# SNAC_7ch_SNES.net
KiCad netlist of a schematic drawn in EAGLE
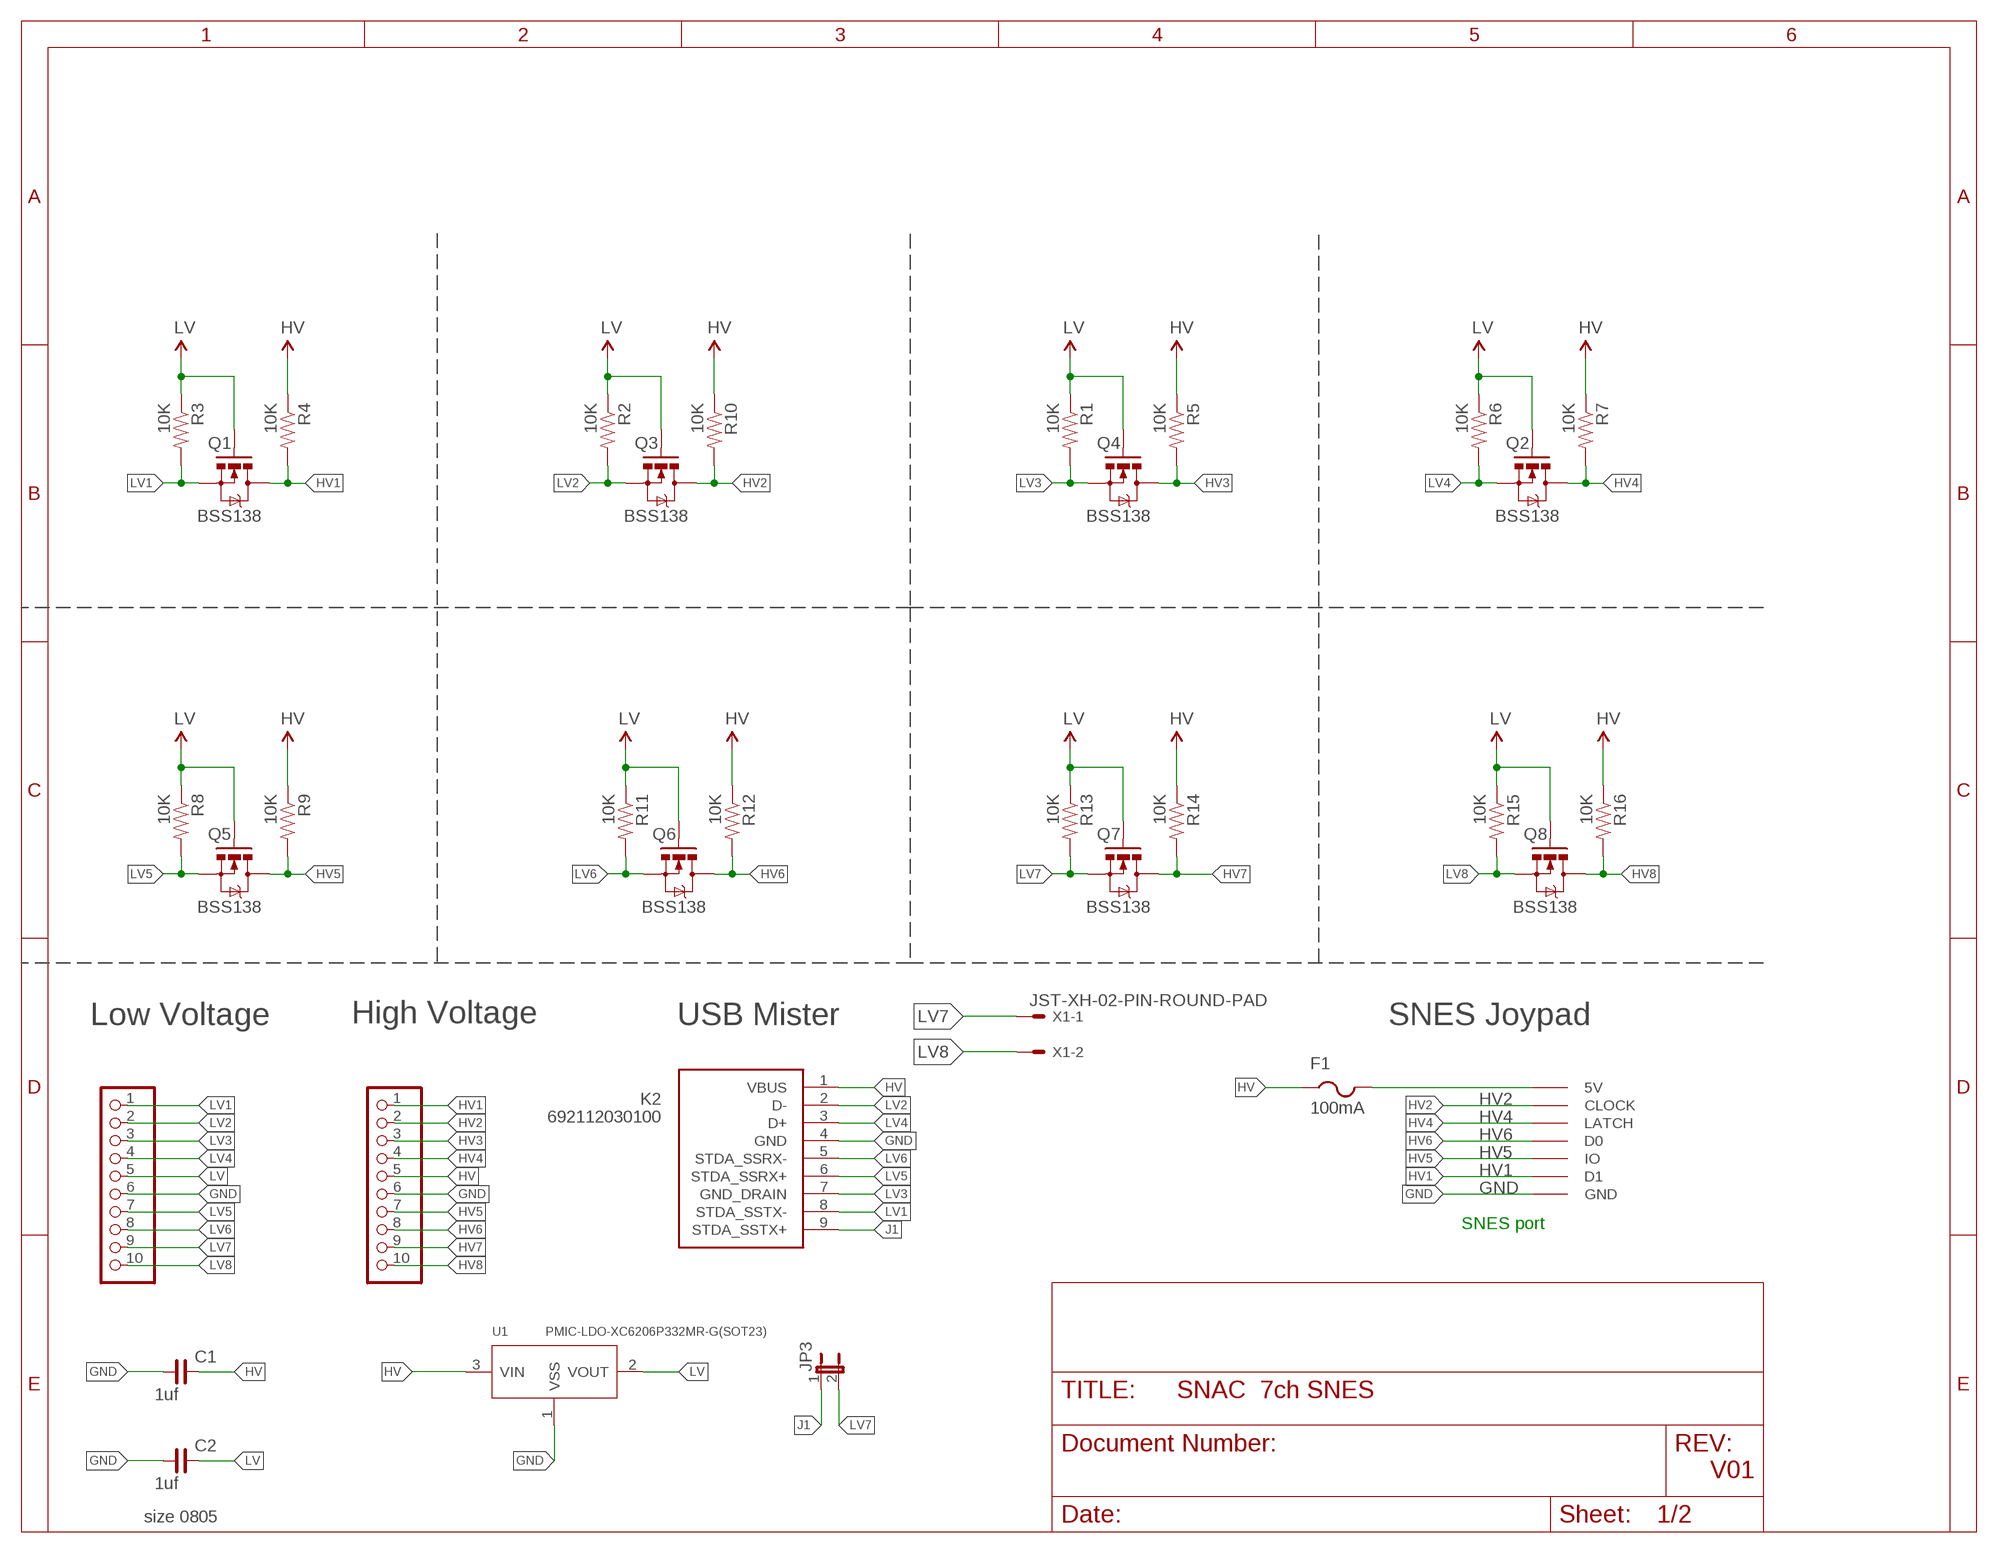
[diagram p0: schematic, sheet 1]

(export (version "E")
  (design (tool "Eeschema 10.0.6"))
  (components
    (comp (ref "C1")
      (value "1uf")
      (footprint "eagle-import:C0805")
      (libsource (lib "eagle-import") (part "C_0805"))
    )
    (comp (ref "C2")
      (value "1uf")
      (footprint "eagle-import:C0805")
      (libsource (lib "eagle-import") (part "C_0805"))
    )
    (comp (ref "F1")
      (value "100mA")
      (footprint "eagle-import:R1206")
      (libsource (lib "eagle-import") (part "PTCFUSE-1206"))
    )
    (comp (ref "JP1")
      (value "PINHD-1X10_2.54-S")
      (footprint "eagle-import:1X10-S")
      (libsource (lib "eagle-import") (part "PINHD-1X10_2.54-S"))
    )
    (comp (ref "JP2")
      (value "PINHD-1X10_2.54-S")
      (footprint "eagle-import:1X10-S")
      (libsource (lib "eagle-import") (part "PINHD-1X10_2.54-S"))
    )
    (comp (ref "JP3")
      (value "JUMPER-2PTH")
      (footprint "eagle-import:1X02")
      (libsource (lib "eagle-import") (part "JUMPER-2PTH"))
    )
    (comp (ref "K2")
      (value "692112030100")
      (footprint "eagle-import:692112030100")
      (libsource (lib "eagle-import") (part "692112030100"))
    )
    (comp (ref "Q1")
      (value "BSS138")
      (footprint "eagle-import:SOT23-3")
      (libsource (lib "eagle-import") (part "MOSFET-NCHANNELSMD"))
    )
    (comp (ref "Q2")
      (value "BSS138")
      (footprint "eagle-import:SOT23-3")
      (libsource (lib "eagle-import") (part "MOSFET-NCHANNELSMD"))
    )
    (comp (ref "Q3")
      (value "BSS138")
      (footprint "eagle-import:SOT23-3")
      (libsource (lib "eagle-import") (part "MOSFET-NCHANNELSMD"))
    )
    (comp (ref "Q4")
      (value "BSS138")
      (footprint "eagle-import:SOT23-3")
      (libsource (lib "eagle-import") (part "MOSFET-NCHANNELSMD"))
    )
    (comp (ref "Q5")
      (value "BSS138")
      (footprint "eagle-import:SOT23-3")
      (libsource (lib "eagle-import") (part "MOSFET-NCHANNELSMD"))
    )
    (comp (ref "Q6")
      (value "BSS138")
      (footprint "eagle-import:SOT23-3")
      (libsource (lib "eagle-import") (part "MOSFET-NCHANNELSMD"))
    )
    (comp (ref "Q7")
      (value "BSS138")
      (footprint "eagle-import:SOT23-3")
      (libsource (lib "eagle-import") (part "MOSFET-NCHANNELSMD"))
    )
    (comp (ref "Q8")
      (value "BSS138")
      (footprint "eagle-import:SOT23-3")
      (libsource (lib "eagle-import") (part "MOSFET-NCHANNELSMD"))
    )
    (comp (ref "R1")
      (value "10K")
      (footprint "eagle-import:0603-RES")
      (libsource (lib "eagle-import") (part "RESISTOR0603-RES"))
    )
    (comp (ref "R2")
      (value "10K")
      (footprint "eagle-import:0603-RES")
      (libsource (lib "eagle-import") (part "RESISTOR0603-RES"))
    )
    (comp (ref "R3")
      (value "10K")
      (footprint "eagle-import:0603-RES")
      (libsource (lib "eagle-import") (part "RESISTOR0603-RES"))
    )
    (comp (ref "R4")
      (value "10K")
      (footprint "eagle-import:0603-RES")
      (libsource (lib "eagle-import") (part "RESISTOR0603-RES"))
    )
    (comp (ref "R5")
      (value "10K")
      (footprint "eagle-import:0603-RES")
      (libsource (lib "eagle-import") (part "RESISTOR0603-RES"))
    )
    (comp (ref "R6")
      (value "10K")
      (footprint "eagle-import:0603-RES")
      (libsource (lib "eagle-import") (part "RESISTOR0603-RES"))
    )
    (comp (ref "R7")
      (value "10K")
      (footprint "eagle-import:0603-RES")
      (libsource (lib "eagle-import") (part "RESISTOR0603-RES"))
    )
    (comp (ref "R8")
      (value "10K")
      (footprint "eagle-import:0603-RES")
      (libsource (lib "eagle-import") (part "RESISTOR0603-RES"))
    )
    (comp (ref "R9")
      (value "10K")
      (footprint "eagle-import:0603-RES")
      (libsource (lib "eagle-import") (part "RESISTOR0603-RES"))
    )
    (comp (ref "R10")
      (value "10K")
      (footprint "eagle-import:0603-RES")
      (libsource (lib "eagle-import") (part "RESISTOR0603-RES"))
    )
    (comp (ref "R11")
      (value "10K")
      (footprint "eagle-import:0603-RES")
      (libsource (lib "eagle-import") (part "RESISTOR0603-RES"))
    )
    (comp (ref "R12")
      (value "10K")
      (footprint "eagle-import:0603-RES")
      (libsource (lib "eagle-import") (part "RESISTOR0603-RES"))
    )
    (comp (ref "R13")
      (value "10K")
      (footprint "eagle-import:0603-RES")
      (libsource (lib "eagle-import") (part "RESISTOR0603-RES"))
    )
    (comp (ref "R14")
      (value "10K")
      (footprint "eagle-import:0603-RES")
      (libsource (lib "eagle-import") (part "RESISTOR0603-RES"))
    )
    (comp (ref "R15")
      (value "10K")
      (footprint "eagle-import:0603-RES")
      (libsource (lib "eagle-import") (part "RESISTOR0603-RES"))
    )
    (comp (ref "R16")
      (value "10K")
      (footprint "eagle-import:0603-RES")
      (libsource (lib "eagle-import") (part "RESISTOR0603-RES"))
    )
    (comp (ref "U$3")
      (value "SNESCONN")
      (footprint "eagle-import:SNESCONN")
      (libsource (lib "eagle-import") (part "SNESCONN"))
    )
    (comp (ref "U1")
      (value "PMIC-LDO-XC6206P332MR-G(SOT23)")
      (footprint "eagle-import:SOT-23")
      (fields (field (name "MF") "Torex") (field (name "MP") "XC6206P332MR-G"))
      (libsource (lib "eagle-import") (part "PMIC-LDO-XC6206P332MR-G(SOT23)"))
    )
    (comp (ref "X1")
      (value "JST-XH-02-PIN-ROUND-PAD")
      (footprint "eagle-import:JST-XH-02-PACKAGE-ROUND-PAD")
      (libsource (lib "eagle-import") (part "JST-XH-02-PIN-ROUND-PAD"))
    )
  )
  (nets
    (net (code "1") (name "GND") (class "Default")
      (node (ref "C1") (pin "1") (pinfunction "1_1") (pintype "passive"))
      (node (ref "C2") (pin "1") (pinfunction "1_1") (pintype "passive"))
      (node (ref "JP1") (pin "6") (pinfunction "6_6") (pintype "passive"))
      (node (ref "JP2") (pin "6") (pinfunction "6_6") (pintype "passive"))
      (node (ref "K2") (pin "4") (pinfunction "GND_4") (pintype "bidirectional"))
      (node (ref "U$3") (pin "GND") (pinfunction "GND_GND") (pintype "power_in"))
      (node (ref "U1") (pin "1") (pinfunction "VSS_1") (pintype "power_in"))
    )
    (net (code "2") (name "HV") (class "Default")
      (node (ref "C1") (pin "2") (pinfunction "2_2") (pintype "passive"))
      (node (ref "F1") (pin "1") (pinfunction "1_1") (pintype "passive"))
      (node (ref "JP2") (pin "5") (pinfunction "5_5") (pintype "passive"))
      (node (ref "K2") (pin "1") (pinfunction "VBUS_1") (pintype "bidirectional"))
      (node (ref "R10") (pin "1") (pinfunction "1_1") (pintype "passive"))
      (node (ref "R12") (pin "1") (pinfunction "1_1") (pintype "passive"))
      (node (ref "R14") (pin "1") (pinfunction "1_1") (pintype "passive"))
      (node (ref "R16") (pin "1") (pinfunction "1_1") (pintype "passive"))
      (node (ref "R4") (pin "1") (pinfunction "1_1") (pintype "passive"))
      (node (ref "R5") (pin "1") (pinfunction "1_1") (pintype "passive"))
      (node (ref "R7") (pin "1") (pinfunction "1_1") (pintype "passive"))
      (node (ref "R9") (pin "1") (pinfunction "1_1") (pintype "passive"))
      (node (ref "U1") (pin "3") (pinfunction "VIN_3") (pintype "input"))
    )
    (net (code "3") (name "HV1") (class "Default")
      (node (ref "JP2") (pin "1") (pinfunction "1_1") (pintype "passive"))
      (node (ref "Q1") (pin "3") (pinfunction "D_3") (pintype "passive"))
      (node (ref "R4") (pin "2") (pinfunction "2_2") (pintype "passive"))
      (node (ref "U$3") (pin "D1") (pinfunction "D1_D1") (pintype "bidirectional"))
    )
    (net (code "4") (name "HV2") (class "Default")
      (node (ref "JP2") (pin "2") (pinfunction "2_2") (pintype "passive"))
      (node (ref "Q3") (pin "3") (pinfunction "D_3") (pintype "passive"))
      (node (ref "R10") (pin "2") (pinfunction "2_2") (pintype "passive"))
      (node (ref "U$3") (pin "CLOCK") (pinfunction "CLOCK_CLOCK") (pintype "input"))
    )
    (net (code "5") (name "HV3") (class "Default")
      (node (ref "JP2") (pin "3") (pinfunction "3_3") (pintype "passive"))
      (node (ref "Q4") (pin "3") (pinfunction "D_3") (pintype "passive"))
      (node (ref "R5") (pin "2") (pinfunction "2_2") (pintype "passive"))
    )
    (net (code "6") (name "HV4") (class "Default")
      (node (ref "JP2") (pin "4") (pinfunction "4_4") (pintype "passive"))
      (node (ref "Q2") (pin "3") (pinfunction "D_3") (pintype "passive"))
      (node (ref "R7") (pin "2") (pinfunction "2_2") (pintype "passive"))
      (node (ref "U$3") (pin "LATCH") (pinfunction "LATCH_LATCH") (pintype "input"))
    )
    (net (code "7") (name "HV5") (class "Default")
      (node (ref "JP2") (pin "7") (pinfunction "7_7") (pintype "passive"))
      (node (ref "Q5") (pin "3") (pinfunction "D_3") (pintype "passive"))
      (node (ref "R9") (pin "2") (pinfunction "2_2") (pintype "passive"))
      (node (ref "U$3") (pin "IO") (pinfunction "IO_IO") (pintype "bidirectional"))
    )
    (net (code "8") (name "HV6") (class "Default")
      (node (ref "JP2") (pin "8") (pinfunction "8_8") (pintype "passive"))
      (node (ref "Q6") (pin "3") (pinfunction "D_3") (pintype "passive"))
      (node (ref "R12") (pin "2") (pinfunction "2_2") (pintype "passive"))
      (node (ref "U$3") (pin "D0") (pinfunction "D0_D0") (pintype "bidirectional"))
    )
    (net (code "9") (name "HV7") (class "Default")
      (node (ref "JP2") (pin "9") (pinfunction "9_9") (pintype "passive"))
      (node (ref "Q7") (pin "3") (pinfunction "D_3") (pintype "passive"))
      (node (ref "R14") (pin "2") (pinfunction "2_2") (pintype "passive"))
    )
    (net (code "10") (name "HV8") (class "Default")
      (node (ref "JP2") (pin "10") (pinfunction "10_10") (pintype "passive"))
      (node (ref "Q8") (pin "3") (pinfunction "D_3") (pintype "passive"))
      (node (ref "R16") (pin "2") (pinfunction "2_2") (pintype "passive"))
    )
    (net (code "11") (name "J1") (class "Default")
      (node (ref "JP3") (pin "1") (pinfunction "1_1") (pintype "passive"))
      (node (ref "K2") (pin "9") (pinfunction "STDA_SSTX+_9") (pintype "bidirectional"))
    )
    (net (code "12") (name "LV") (class "Default")
      (node (ref "C2") (pin "2") (pinfunction "2_2") (pintype "passive"))
      (node (ref "JP1") (pin "5") (pinfunction "5_5") (pintype "passive"))
      (node (ref "Q1") (pin "1") (pinfunction "G_1") (pintype "passive"))
      (node (ref "Q2") (pin "1") (pinfunction "G_1") (pintype "passive"))
      (node (ref "Q3") (pin "1") (pinfunction "G_1") (pintype "passive"))
      (node (ref "Q4") (pin "1") (pinfunction "G_1") (pintype "passive"))
      (node (ref "Q5") (pin "1") (pinfunction "G_1") (pintype "passive"))
      (node (ref "Q6") (pin "1") (pinfunction "G_1") (pintype "passive"))
      (node (ref "Q7") (pin "1") (pinfunction "G_1") (pintype "passive"))
      (node (ref "Q8") (pin "1") (pinfunction "G_1") (pintype "passive"))
      (node (ref "R1") (pin "1") (pinfunction "1_1") (pintype "passive"))
      (node (ref "R11") (pin "1") (pinfunction "1_1") (pintype "passive"))
      (node (ref "R13") (pin "1") (pinfunction "1_1") (pintype "passive"))
      (node (ref "R15") (pin "1") (pinfunction "1_1") (pintype "passive"))
      (node (ref "R2") (pin "1") (pinfunction "1_1") (pintype "passive"))
      (node (ref "R3") (pin "1") (pinfunction "1_1") (pintype "passive"))
      (node (ref "R6") (pin "1") (pinfunction "1_1") (pintype "passive"))
      (node (ref "R8") (pin "1") (pinfunction "1_1") (pintype "passive"))
      (node (ref "U1") (pin "2") (pinfunction "VOUT_2") (pintype "output"))
    )
    (net (code "13") (name "LV1") (class "Default")
      (node (ref "JP1") (pin "1") (pinfunction "1_1") (pintype "passive"))
      (node (ref "K2") (pin "8") (pinfunction "STDA_SSTX-_8") (pintype "bidirectional"))
      (node (ref "Q1") (pin "2") (pinfunction "S_2") (pintype "passive"))
      (node (ref "R3") (pin "2") (pinfunction "2_2") (pintype "passive"))
    )
    (net (code "14") (name "LV2") (class "Default")
      (node (ref "JP1") (pin "2") (pinfunction "2_2") (pintype "passive"))
      (node (ref "K2") (pin "2") (pinfunction "D-_2") (pintype "bidirectional"))
      (node (ref "Q3") (pin "2") (pinfunction "S_2") (pintype "passive"))
      (node (ref "R2") (pin "2") (pinfunction "2_2") (pintype "passive"))
    )
    (net (code "15") (name "LV3") (class "Default")
      (node (ref "JP1") (pin "3") (pinfunction "3_3") (pintype "passive"))
      (node (ref "K2") (pin "7") (pinfunction "GND_DRAIN_7") (pintype "bidirectional"))
      (node (ref "Q4") (pin "2") (pinfunction "S_2") (pintype "passive"))
      (node (ref "R1") (pin "2") (pinfunction "2_2") (pintype "passive"))
    )
    (net (code "16") (name "LV4") (class "Default")
      (node (ref "JP1") (pin "4") (pinfunction "4_4") (pintype "passive"))
      (node (ref "K2") (pin "3") (pinfunction "D+_3") (pintype "bidirectional"))
      (node (ref "Q2") (pin "2") (pinfunction "S_2") (pintype "passive"))
      (node (ref "R6") (pin "2") (pinfunction "2_2") (pintype "passive"))
    )
    (net (code "17") (name "LV5") (class "Default")
      (node (ref "JP1") (pin "7") (pinfunction "7_7") (pintype "passive"))
      (node (ref "K2") (pin "6") (pinfunction "STDA_SSRX+_6") (pintype "bidirectional"))
      (node (ref "Q5") (pin "2") (pinfunction "S_2") (pintype "passive"))
      (node (ref "R8") (pin "2") (pinfunction "2_2") (pintype "passive"))
    )
    (net (code "18") (name "LV6") (class "Default")
      (node (ref "JP1") (pin "8") (pinfunction "8_8") (pintype "passive"))
      (node (ref "K2") (pin "5") (pinfunction "STDA_SSRX-_5") (pintype "bidirectional"))
      (node (ref "Q6") (pin "2") (pinfunction "S_2") (pintype "passive"))
      (node (ref "R11") (pin "2") (pinfunction "2_2") (pintype "passive"))
    )
    (net (code "19") (name "LV7") (class "Default")
      (node (ref "JP1") (pin "9") (pinfunction "9_9") (pintype "passive"))
      (node (ref "JP3") (pin "2") (pinfunction "2_2") (pintype "passive"))
      (node (ref "Q7") (pin "2") (pinfunction "S_2") (pintype "passive"))
      (node (ref "R13") (pin "2") (pinfunction "2_2") (pintype "passive"))
      (node (ref "X1") (pin "1") (pinfunction "S_1") (pintype "passive"))
    )
    (net (code "20") (name "LV8") (class "Default")
      (node (ref "JP1") (pin "10") (pinfunction "10_10") (pintype "passive"))
      (node (ref "Q8") (pin "2") (pinfunction "S_2") (pintype "passive"))
      (node (ref "R15") (pin "2") (pinfunction "2_2") (pintype "passive"))
      (node (ref "X1") (pin "2") (pinfunction "S_2") (pintype "passive"))
    )
    (net (code "21") (name "Net-(F1-Pad2)") (class "Default")
      (node (ref "F1") (pin "2") (pinfunction "2_2") (pintype "passive"))
      (node (ref "U$3") (pin "5V") (pinfunction "5V_5V") (pintype "input"))
    )
  )
)
